# RTM_Connector.net
KiCad netlist of a schematic drawn in Altium Designer
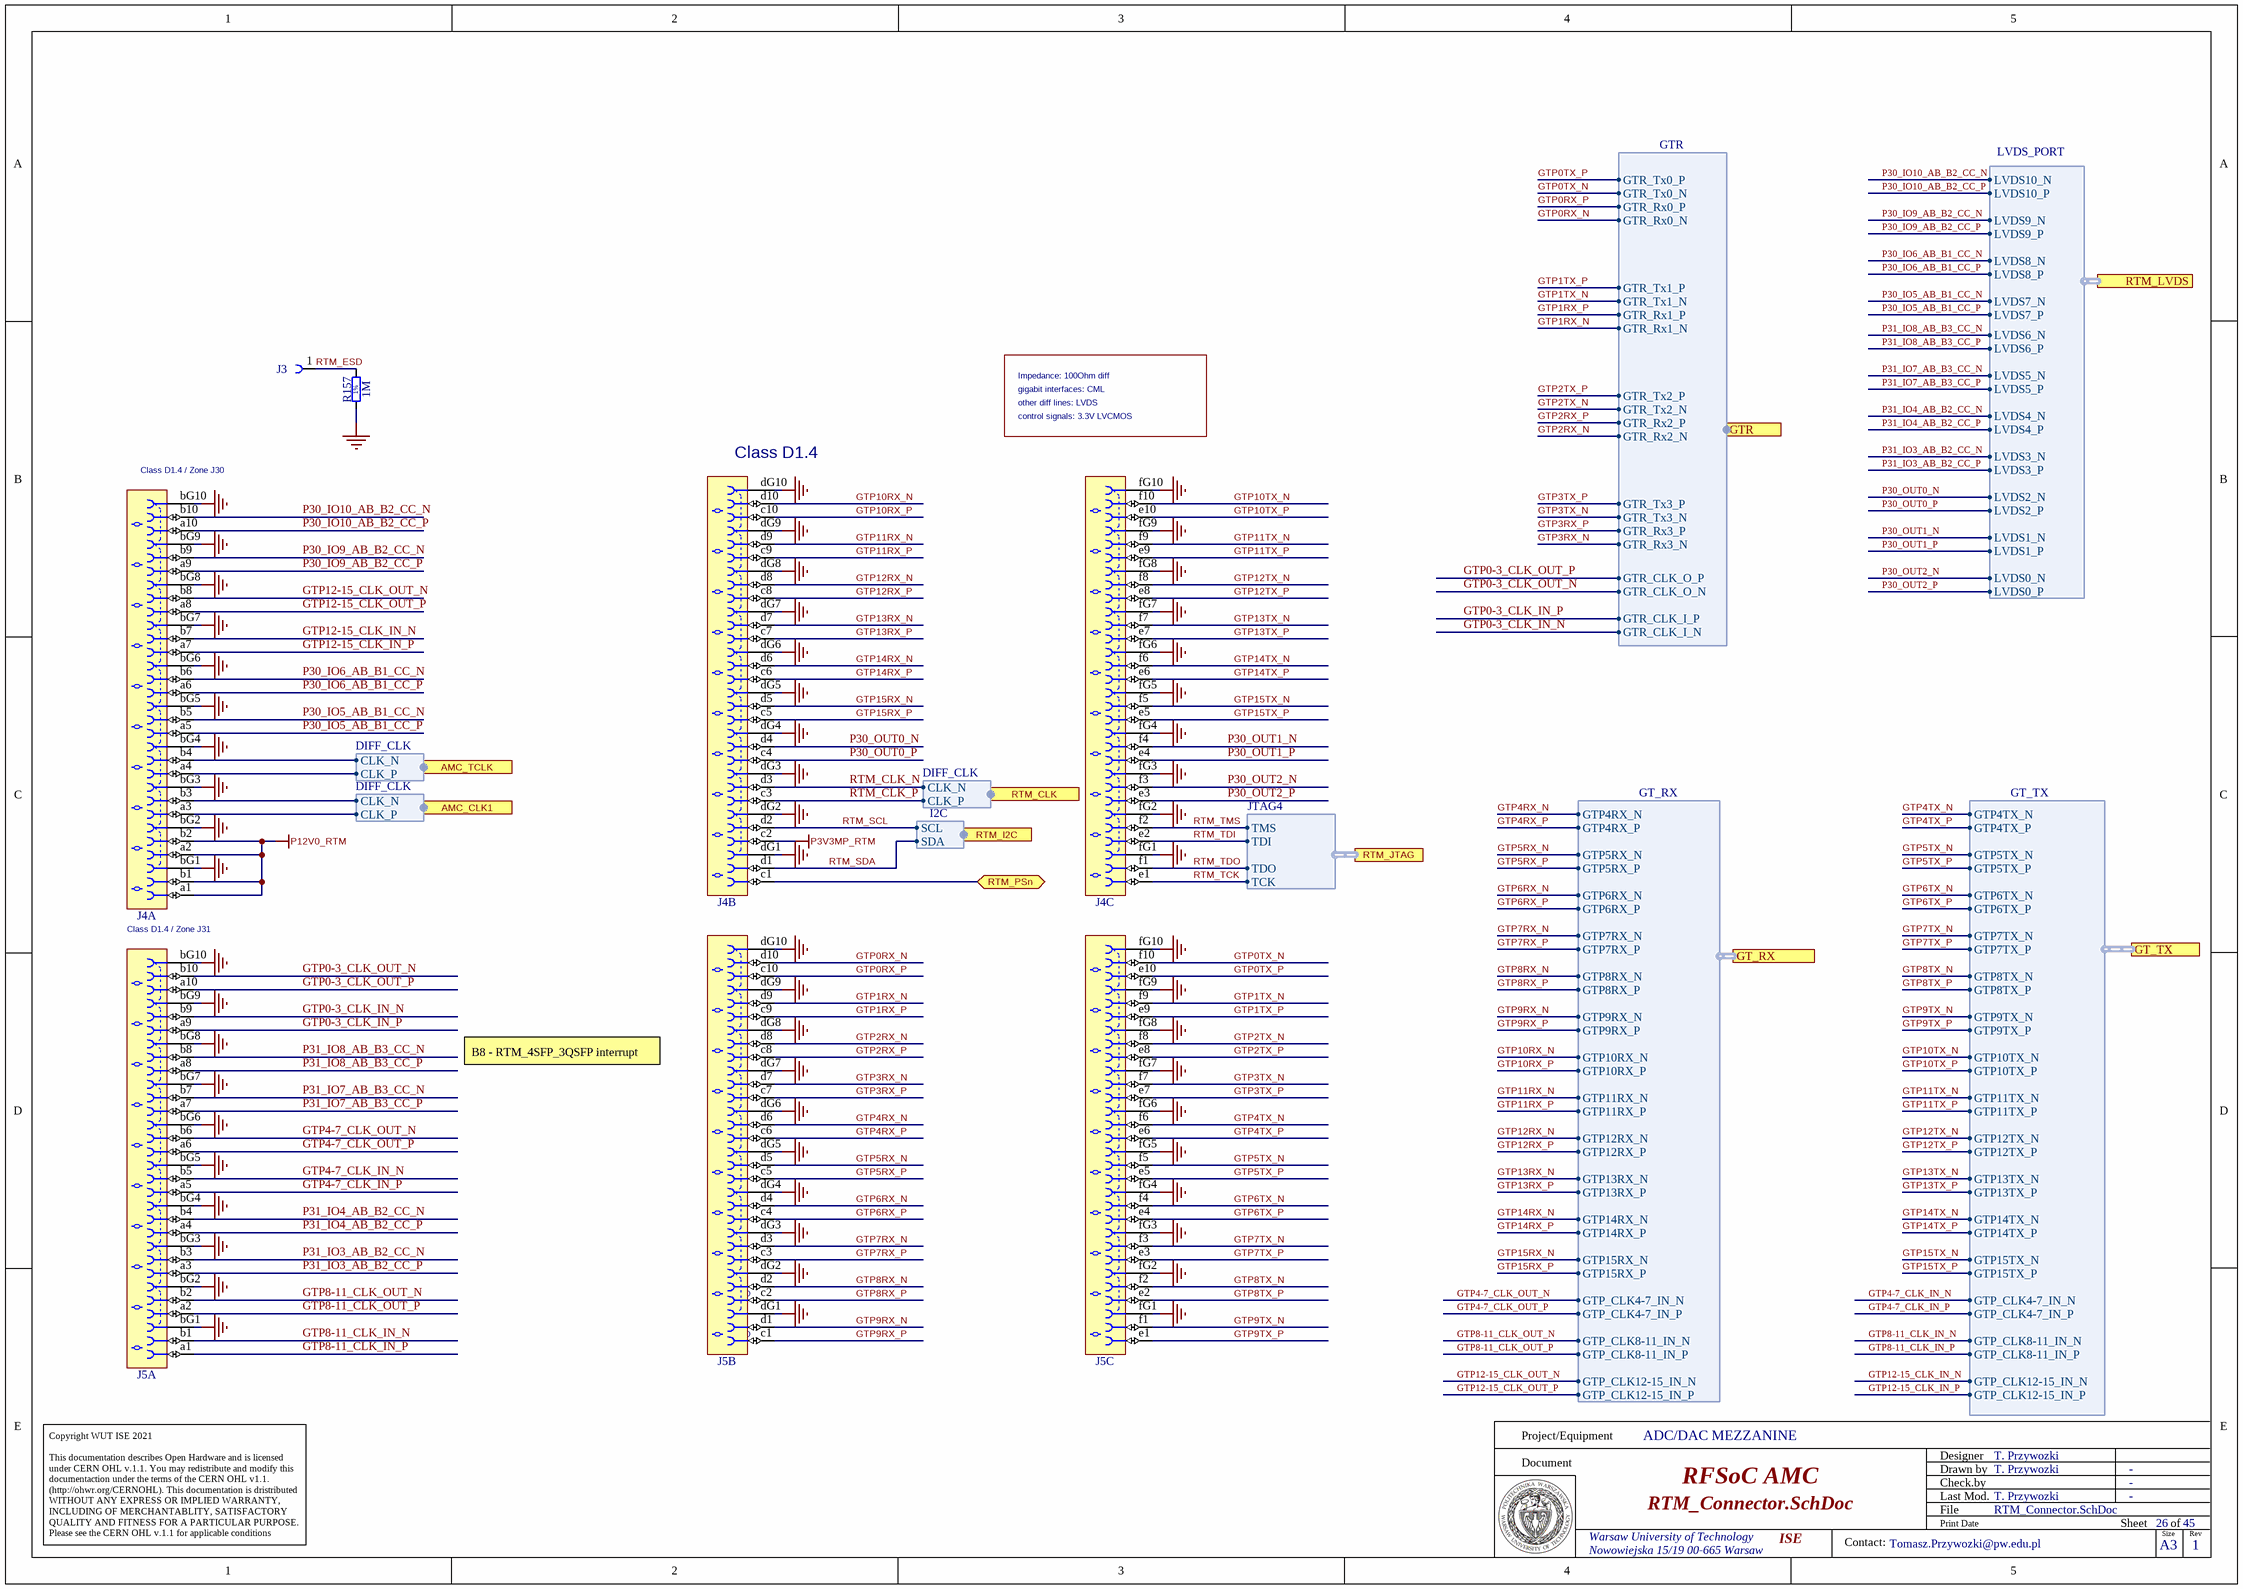
[diagram p0: RTM_Connector.SchDoc]

(export (version "E")
  (design (tool "Eeschema 10.0.6"))
  (components
    (comp (ref "J3")
      (value "~")
      (footprint "TYCO_5120913-1")
      (description "Single Pin Female")
      (fields
        (field (name "MANUFACTURER PART NUMBER") "5120913-1")
        (field (name "MANUFACTURER") "TYCO ELECTRONICS")
        (field (name "AUTHOR") "CERN DEM JLC")
      )
      (libsource (lib "Connectors") (part "Single Pin Female"))
    )
    (comp (ref "J4")
      (value "Advanced TCA")
      (footprint "TYCO_6469081-1")
      (description "Connector 60 ATCA Female 30 Pairs (60 Signals) + 3x10 Ground")
      (fields
        (field (name "MANUFACTURER PART NUMBER") "6469081-1")
        (field (name "MANUFACTURER") "TYCO ELECTRONICS")
        (field (name "AUTHOR") "CERN DEM JLC")
      )
      (libsource (lib "Connectors") (part "Connector ATCA 60+30 Female"))
    )
    (comp (ref "J5")
      (value "Advanced TCA")
      (footprint "TYCO_6469081-1")
      (description "Connector 60 ATCA Female 30 Pairs (60 Signals) + 3x10 Ground")
      (fields
        (field (name "MANUFACTURER PART NUMBER") "6469081-1")
        (field (name "MANUFACTURER") "TYCO ELECTRONICS")
        (field (name "AUTHOR") "CERN DEM JLC")
      )
      (libsource (lib "Connectors") (part "Connector ATCA 60+30 Female"))
    )
    (comp (ref "R157")
      (value "1M")
      (footprint "RESC5025X65N")
      (description "Resistor - 1%")
      (fields
        (field (name "MANUFACTURER PART NUMBER") "R2010_1M_1%_0.5W_200PPM")
        (field (name "MANUFACTURER") "GENERIC")
        (field (name "AUTHOR") "CERN DEM JLC")
      )
      (libsource (lib "Resistors") (part "Resistor - 1%"))
    )
  )
  (nets
    (net (code "8") (name "/GTP0-3_CLK_IN_N") (class "Default")
      (node (ref "J5") (pin "b9") (pinfunction "b9_b9") (pintype "bidirectional"))
    )
    (net (code "9") (name "/GTP0-3_CLK_IN_P") (class "Default")
      (node (ref "J5") (pin "a9") (pinfunction "a9_a9") (pintype "bidirectional"))
    )
    (net (code "10") (name "/GTP0-3_CLK_OUT_N") (class "Default")
      (node (ref "J5") (pin "b10") (pinfunction "b10_b10") (pintype "bidirectional"))
    )
    (net (code "11") (name "/GTP0-3_CLK_OUT_P") (class "Default")
      (node (ref "J5") (pin "a10") (pinfunction "a10_a10") (pintype "bidirectional"))
    )
    (net (code "12") (name "/GTP0RX_N") (class "Default")
      (node (ref "J5") (pin "d10") (pinfunction "d10_d10") (pintype "bidirectional"))
    )
    (net (code "13") (name "/GTP0RX_P") (class "Default")
      (node (ref "J5") (pin "c10") (pinfunction "c10_c10") (pintype "bidirectional"))
    )
    (net (code "14") (name "/GTP0TX_N") (class "Default")
      (node (ref "J5") (pin "f10") (pinfunction "f10_f10") (pintype "bidirectional"))
    )
    (net (code "15") (name "/GTP0TX_P") (class "Default")
      (node (ref "J5") (pin "e10") (pinfunction "e10_e10") (pintype "bidirectional"))
    )
    (net (code "16") (name "/GTP1RX_N") (class "Default")
      (node (ref "J5") (pin "d9") (pinfunction "d9_d9") (pintype "bidirectional"))
    )
    (net (code "17") (name "/GTP1RX_P") (class "Default")
      (node (ref "J5") (pin "c9") (pinfunction "c9_c9") (pintype "bidirectional"))
    )
    (net (code "18") (name "/GTP1TX_N") (class "Default")
      (node (ref "J5") (pin "f9") (pinfunction "f9_f9") (pintype "bidirectional"))
    )
    (net (code "19") (name "/GTP1TX_P") (class "Default")
      (node (ref "J5") (pin "e9") (pinfunction "e9_e9") (pintype "bidirectional"))
    )
    (net (code "20") (name "/GTP2RX_N") (class "Default")
      (node (ref "J5") (pin "d8") (pinfunction "d8_d8") (pintype "bidirectional"))
    )
    (net (code "21") (name "/GTP2RX_P") (class "Default")
      (node (ref "J5") (pin "c8") (pinfunction "c8_c8") (pintype "bidirectional"))
    )
    (net (code "22") (name "/GTP2TX_N") (class "Default")
      (node (ref "J5") (pin "f8") (pinfunction "f8_f8") (pintype "bidirectional"))
    )
    (net (code "23") (name "/GTP2TX_P") (class "Default")
      (node (ref "J5") (pin "e8") (pinfunction "e8_e8") (pintype "bidirectional"))
    )
    (net (code "24") (name "/GTP3RX_N") (class "Default")
      (node (ref "J5") (pin "d7") (pinfunction "d7_d7") (pintype "bidirectional"))
    )
    (net (code "25") (name "/GTP3RX_P") (class "Default")
      (node (ref "J5") (pin "c7") (pinfunction "c7_c7") (pintype "bidirectional"))
    )
    (net (code "26") (name "/GTP3TX_N") (class "Default")
      (node (ref "J5") (pin "f7") (pinfunction "f7_f7") (pintype "bidirectional"))
    )
    (net (code "27") (name "/GTP3TX_P") (class "Default")
      (node (ref "J5") (pin "e7") (pinfunction "e7_e7") (pintype "bidirectional"))
    )
    (net (code "28") (name "/GTP4-7_CLK_IN_N") (class "Default")
      (node (ref "J5") (pin "b5") (pinfunction "b5_b5") (pintype "bidirectional"))
    )
    (net (code "29") (name "/GTP4-7_CLK_IN_P") (class "Default")
      (node (ref "J5") (pin "a5") (pinfunction "a5_a5") (pintype "bidirectional"))
    )
    (net (code "30") (name "/GTP4-7_CLK_OUT_N") (class "Default")
      (node (ref "J5") (pin "b6") (pinfunction "b6_b6") (pintype "bidirectional"))
    )
    (net (code "31") (name "/GTP4-7_CLK_OUT_P") (class "Default")
      (node (ref "J5") (pin "a6") (pinfunction "a6_a6") (pintype "bidirectional"))
    )
    (net (code "32") (name "/GTP4RX_N") (class "Default")
      (node (ref "J5") (pin "d6") (pinfunction "d6_d6") (pintype "bidirectional"))
    )
    (net (code "33") (name "/GTP4RX_P") (class "Default")
      (node (ref "J5") (pin "c6") (pinfunction "c6_c6") (pintype "bidirectional"))
    )
    (net (code "34") (name "/GTP4TX_N") (class "Default")
      (node (ref "J5") (pin "f6") (pinfunction "f6_f6") (pintype "bidirectional"))
    )
    (net (code "35") (name "/GTP4TX_P") (class "Default")
      (node (ref "J5") (pin "e6") (pinfunction "e6_e6") (pintype "bidirectional"))
    )
    (net (code "36") (name "/GTP5RX_N") (class "Default")
      (node (ref "J5") (pin "d5") (pinfunction "d5_d5") (pintype "bidirectional"))
    )
    (net (code "37") (name "/GTP5RX_P") (class "Default")
      (node (ref "J5") (pin "c5") (pinfunction "c5_c5") (pintype "bidirectional"))
    )
    (net (code "38") (name "/GTP5TX_N") (class "Default")
      (node (ref "J5") (pin "f5") (pinfunction "f5_f5") (pintype "bidirectional"))
    )
    (net (code "39") (name "/GTP5TX_P") (class "Default")
      (node (ref "J5") (pin "e5") (pinfunction "e5_e5") (pintype "bidirectional"))
    )
    (net (code "40") (name "/GTP6RX_N") (class "Default")
      (node (ref "J5") (pin "d4") (pinfunction "d4_d4") (pintype "bidirectional"))
    )
    (net (code "41") (name "/GTP6RX_P") (class "Default")
      (node (ref "J5") (pin "c4") (pinfunction "c4_c4") (pintype "bidirectional"))
    )
    (net (code "42") (name "/GTP6TX_N") (class "Default")
      (node (ref "J5") (pin "f4") (pinfunction "f4_f4") (pintype "bidirectional"))
    )
    (net (code "43") (name "/GTP6TX_P") (class "Default")
      (node (ref "J5") (pin "e4") (pinfunction "e4_e4") (pintype "bidirectional"))
    )
    (net (code "44") (name "/GTP7RX_N") (class "Default")
      (node (ref "J5") (pin "d3") (pinfunction "d3_d3") (pintype "bidirectional"))
    )
    (net (code "45") (name "/GTP7RX_P") (class "Default")
      (node (ref "J5") (pin "c3") (pinfunction "c3_c3") (pintype "bidirectional"))
    )
    (net (code "46") (name "/GTP7TX_N") (class "Default")
      (node (ref "J5") (pin "f3") (pinfunction "f3_f3") (pintype "bidirectional"))
    )
    (net (code "47") (name "/GTP7TX_P") (class "Default")
      (node (ref "J5") (pin "e3") (pinfunction "e3_e3") (pintype "bidirectional"))
    )
    (net (code "48") (name "/GTP8-11_CLK_IN_N") (class "Default")
      (node (ref "J5") (pin "b1") (pinfunction "b1_b1") (pintype "bidirectional"))
    )
    (net (code "49") (name "/GTP8-11_CLK_IN_P") (class "Default")
      (node (ref "J5") (pin "a1") (pinfunction "a1_a1") (pintype "bidirectional"))
    )
    (net (code "50") (name "/GTP8-11_CLK_OUT_N") (class "Default")
      (node (ref "J5") (pin "b2") (pinfunction "b2_b2") (pintype "bidirectional"))
    )
    (net (code "51") (name "/GTP8-11_CLK_OUT_P") (class "Default")
      (node (ref "J5") (pin "a2") (pinfunction "a2_a2") (pintype "bidirectional"))
    )
    (net (code "52") (name "/GTP8RX_N") (class "Default")
      (node (ref "J5") (pin "d2") (pinfunction "d2_d2") (pintype "bidirectional"))
    )
    (net (code "53") (name "/GTP8RX_P") (class "Default")
      (node (ref "J5") (pin "c2") (pinfunction "c2_c2") (pintype "bidirectional"))
    )
    (net (code "54") (name "/GTP8TX_N") (class "Default")
      (node (ref "J5") (pin "f2") (pinfunction "f2_f2") (pintype "bidirectional"))
    )
    (net (code "55") (name "/GTP8TX_P") (class "Default")
      (node (ref "J5") (pin "e2") (pinfunction "e2_e2") (pintype "bidirectional"))
    )
    (net (code "56") (name "/GTP9RX_N") (class "Default")
      (node (ref "J5") (pin "d1") (pinfunction "d1_d1") (pintype "bidirectional"))
    )
    (net (code "57") (name "/GTP9RX_P") (class "Default")
      (node (ref "J5") (pin "c1") (pinfunction "c1_c1") (pintype "bidirectional"))
    )
    (net (code "58") (name "/GTP9TX_N") (class "Default")
      (node (ref "J5") (pin "f1") (pinfunction "f1_f1") (pintype "bidirectional"))
    )
    (net (code "59") (name "/GTP9TX_P") (class "Default")
      (node (ref "J5") (pin "e1") (pinfunction "e1_e1") (pintype "bidirectional"))
    )
    (net (code "60") (name "/GTP10RX_N") (class "Default")
      (node (ref "J4") (pin "d10") (pinfunction "d10_d10") (pintype "bidirectional"))
    )
    (net (code "61") (name "/GTP10RX_P") (class "Default")
      (node (ref "J4") (pin "c10") (pinfunction "c10_c10") (pintype "bidirectional"))
    )
    (net (code "62") (name "/GTP10TX_N") (class "Default")
      (node (ref "J4") (pin "f10") (pinfunction "f10_f10") (pintype "bidirectional"))
    )
    (net (code "63") (name "/GTP10TX_P") (class "Default")
      (node (ref "J4") (pin "e10") (pinfunction "e10_e10") (pintype "bidirectional"))
    )
    (net (code "64") (name "/GTP11RX_N") (class "Default")
      (node (ref "J4") (pin "d9") (pinfunction "d9_d9") (pintype "bidirectional"))
    )
    (net (code "65") (name "/GTP11RX_P") (class "Default")
      (node (ref "J4") (pin "c9") (pinfunction "c9_c9") (pintype "bidirectional"))
    )
    (net (code "66") (name "/GTP11TX_N") (class "Default")
      (node (ref "J4") (pin "f9") (pinfunction "f9_f9") (pintype "bidirectional"))
    )
    (net (code "67") (name "/GTP11TX_P") (class "Default")
      (node (ref "J4") (pin "e9") (pinfunction "e9_e9") (pintype "bidirectional"))
    )
    (net (code "68") (name "/GTP12-15_CLK_IN_N") (class "Default")
      (node (ref "J4") (pin "b7") (pinfunction "b7_b7") (pintype "bidirectional"))
    )
    (net (code "69") (name "/GTP12-15_CLK_IN_P") (class "Default")
      (node (ref "J4") (pin "a7") (pinfunction "a7_a7") (pintype "bidirectional"))
    )
    (net (code "70") (name "/GTP12-15_CLK_OUT_N") (class "Default")
      (node (ref "J4") (pin "b8") (pinfunction "b8_b8") (pintype "bidirectional"))
    )
    (net (code "71") (name "/GTP12-15_CLK_OUT_P") (class "Default")
      (node (ref "J4") (pin "a8") (pinfunction "a8_a8") (pintype "bidirectional"))
    )
    (net (code "72") (name "/GTP12RX_N") (class "Default")
      (node (ref "J4") (pin "d8") (pinfunction "d8_d8") (pintype "bidirectional"))
    )
    (net (code "73") (name "/GTP12RX_P") (class "Default")
      (node (ref "J4") (pin "c8") (pinfunction "c8_c8") (pintype "bidirectional"))
    )
    (net (code "74") (name "/GTP12TX_N") (class "Default")
      (node (ref "J4") (pin "f8") (pinfunction "f8_f8") (pintype "bidirectional"))
    )
    (net (code "75") (name "/GTP12TX_P") (class "Default")
      (node (ref "J4") (pin "e8") (pinfunction "e8_e8") (pintype "bidirectional"))
    )
    (net (code "76") (name "/GTP13RX_N") (class "Default")
      (node (ref "J4") (pin "d7") (pinfunction "d7_d7") (pintype "bidirectional"))
    )
    (net (code "77") (name "/GTP13RX_P") (class "Default")
      (node (ref "J4") (pin "c7") (pinfunction "c7_c7") (pintype "bidirectional"))
    )
    (net (code "78") (name "/GTP13TX_N") (class "Default")
      (node (ref "J4") (pin "f7") (pinfunction "f7_f7") (pintype "bidirectional"))
    )
    (net (code "79") (name "/GTP13TX_P") (class "Default")
      (node (ref "J4") (pin "e7") (pinfunction "e7_e7") (pintype "bidirectional"))
    )
    (net (code "80") (name "/GTP14RX_N") (class "Default")
      (node (ref "J4") (pin "d6") (pinfunction "d6_d6") (pintype "bidirectional"))
    )
    (net (code "81") (name "/GTP14RX_P") (class "Default")
      (node (ref "J4") (pin "c6") (pinfunction "c6_c6") (pintype "bidirectional"))
    )
    (net (code "82") (name "/GTP14TX_N") (class "Default")
      (node (ref "J4") (pin "f6") (pinfunction "f6_f6") (pintype "bidirectional"))
    )
    (net (code "83") (name "/GTP14TX_P") (class "Default")
      (node (ref "J4") (pin "e6") (pinfunction "e6_e6") (pintype "bidirectional"))
    )
    (net (code "84") (name "/GTP15RX_N") (class "Default")
      (node (ref "J4") (pin "d5") (pinfunction "d5_d5") (pintype "bidirectional"))
    )
    (net (code "85") (name "/GTP15RX_P") (class "Default")
      (node (ref "J4") (pin "c5") (pinfunction "c5_c5") (pintype "bidirectional"))
    )
    (net (code "86") (name "/GTP15TX_N") (class "Default")
      (node (ref "J4") (pin "f5") (pinfunction "f5_f5") (pintype "bidirectional"))
    )
    (net (code "87") (name "/GTP15TX_P") (class "Default")
      (node (ref "J4") (pin "e5") (pinfunction "e5_e5") (pintype "bidirectional"))
    )
    (net (code "88") (name "/P30_IO5_AB_B1_CC_N") (class "Default")
      (node (ref "J4") (pin "b5") (pinfunction "b5_b5") (pintype "bidirectional"))
    )
    (net (code "89") (name "/P30_IO5_AB_B1_CC_P") (class "Default")
      (node (ref "J4") (pin "a5") (pinfunction "a5_a5") (pintype "bidirectional"))
    )
    (net (code "90") (name "/P30_IO6_AB_B1_CC_N") (class "Default")
      (node (ref "J4") (pin "b6") (pinfunction "b6_b6") (pintype "bidirectional"))
    )
    (net (code "91") (name "/P30_IO6_AB_B1_CC_P") (class "Default")
      (node (ref "J4") (pin "a6") (pinfunction "a6_a6") (pintype "bidirectional"))
    )
    (net (code "92") (name "/P30_IO9_AB_B2_CC_N") (class "Default")
      (node (ref "J4") (pin "b9") (pinfunction "b9_b9") (pintype "bidirectional"))
    )
    (net (code "93") (name "/P30_IO9_AB_B2_CC_P") (class "Default")
      (node (ref "J4") (pin "a9") (pinfunction "a9_a9") (pintype "bidirectional"))
    )
    (net (code "94") (name "/P30_IO10_AB_B2_CC_N") (class "Default")
      (node (ref "J4") (pin "b10") (pinfunction "b10_b10") (pintype "bidirectional"))
    )
    (net (code "95") (name "/P30_IO10_AB_B2_CC_P") (class "Default")
      (node (ref "J4") (pin "a10") (pinfunction "a10_a10") (pintype "bidirectional"))
    )
    (net (code "96") (name "/P30_OUT0_N") (class "Default")
      (node (ref "J4") (pin "d4") (pinfunction "d4_d4") (pintype "bidirectional"))
    )
    (net (code "97") (name "/P30_OUT0_P") (class "Default")
      (node (ref "J4") (pin "c4") (pinfunction "c4_c4") (pintype "bidirectional"))
    )
    (net (code "98") (name "/P30_OUT1_N") (class "Default")
      (node (ref "J4") (pin "f4") (pinfunction "f4_f4") (pintype "bidirectional"))
    )
    (net (code "99") (name "/P30_OUT1_P") (class "Default")
      (node (ref "J4") (pin "e4") (pinfunction "e4_e4") (pintype "bidirectional"))
    )
    (net (code "100") (name "/P30_OUT2_N") (class "Default")
      (node (ref "J4") (pin "f3") (pinfunction "f3_f3") (pintype "bidirectional"))
    )
    (net (code "101") (name "/P30_OUT2_P") (class "Default")
      (node (ref "J4") (pin "e3") (pinfunction "e3_e3") (pintype "bidirectional"))
    )
    (net (code "102") (name "/P31_IO3_AB_B2_CC_N") (class "Default")
      (node (ref "J5") (pin "b3") (pinfunction "b3_b3") (pintype "bidirectional"))
    )
    (net (code "103") (name "/P31_IO3_AB_B2_CC_P") (class "Default")
      (node (ref "J5") (pin "a3") (pinfunction "a3_a3") (pintype "bidirectional"))
    )
    (net (code "104") (name "/P31_IO4_AB_B2_CC_N") (class "Default")
      (node (ref "J5") (pin "b4") (pinfunction "b4_b4") (pintype "bidirectional"))
    )
    (net (code "105") (name "/P31_IO4_AB_B2_CC_P") (class "Default")
      (node (ref "J5") (pin "a4") (pinfunction "a4_a4") (pintype "bidirectional"))
    )
    (net (code "106") (name "/P31_IO7_AB_B3_CC_N") (class "Default")
      (node (ref "J5") (pin "b7") (pinfunction "b7_b7") (pintype "bidirectional"))
    )
    (net (code "107") (name "/P31_IO7_AB_B3_CC_P") (class "Default")
      (node (ref "J5") (pin "a7") (pinfunction "a7_a7") (pintype "bidirectional"))
    )
    (net (code "108") (name "/P31_IO8_AB_B3_CC_N") (class "Default")
      (node (ref "J5") (pin "b8") (pinfunction "b8_b8") (pintype "bidirectional"))
    )
    (net (code "109") (name "/P31_IO8_AB_B3_CC_P") (class "Default")
      (node (ref "J5") (pin "a8") (pinfunction "a8_a8") (pintype "bidirectional"))
    )
    (net (code "110") (name "/RTM_CLK_N") (class "Default")
      (node (ref "J4") (pin "d3") (pinfunction "d3_d3") (pintype "bidirectional"))
    )
    (net (code "111") (name "/RTM_CLK_P") (class "Default")
      (node (ref "J4") (pin "c3") (pinfunction "c3_c3") (pintype "bidirectional"))
    )
    (net (code "112") (name "/RTM_ESD") (class "Default")
      (node (ref "J3") (pin "1") (pinfunction "1_1") (pintype "bidirectional"))
      (node (ref "R157") (pin "2") (pinfunction "2_2") (pintype "passive"))
    )
    (net (code "113") (name "/RTM_PSn") (class "Default")
      (node (ref "J4") (pin "c1") (pinfunction "c1_c1") (pintype "bidirectional"))
    )
    (net (code "114") (name "/RTM_SCL") (class "Default")
      (node (ref "J4") (pin "d2") (pinfunction "d2_d2") (pintype "bidirectional"))
    )
    (net (code "115") (name "/RTM_SDA") (class "Default")
      (node (ref "J4") (pin "d1") (pinfunction "d1_d1") (pintype "bidirectional"))
    )
    (net (code "116") (name "/RTM_TCK") (class "Default")
      (node (ref "J4") (pin "e1") (pinfunction "e1_e1") (pintype "bidirectional"))
    )
    (net (code "117") (name "/RTM_TDI") (class "Default")
      (node (ref "J4") (pin "e2") (pinfunction "e2_e2") (pintype "bidirectional"))
    )
    (net (code "118") (name "/RTM_TDO") (class "Default")
      (node (ref "J4") (pin "f1") (pinfunction "f1_f1") (pintype "bidirectional"))
    )
    (net (code "119") (name "/RTM_TMS") (class "Default")
      (node (ref "J4") (pin "f2") (pinfunction "f2_f2") (pintype "bidirectional"))
    )
    (net (code "127") (name "GND") (class "Default")
      (node (ref "J4") (pin "bG1") (pinfunction "bG1_bG1") (pintype "power_in"))
      (node (ref "J4") (pin "bG10") (pinfunction "bG10_bG10") (pintype "power_in"))
      (node (ref "J4") (pin "bG2") (pinfunction "bG2_bG2") (pintype "power_in"))
      (node (ref "J4") (pin "bG3") (pinfunction "bG3_bG3") (pintype "power_in"))
      (node (ref "J4") (pin "bG4") (pinfunction "bG4_bG4") (pintype "power_in"))
      (node (ref "J4") (pin "bG5") (pinfunction "bG5_bG5") (pintype "power_in"))
      (node (ref "J4") (pin "bG6") (pinfunction "bG6_bG6") (pintype "power_in"))
      (node (ref "J4") (pin "bG7") (pinfunction "bG7_bG7") (pintype "power_in"))
      (node (ref "J4") (pin "bG8") (pinfunction "bG8_bG8") (pintype "power_in"))
      (node (ref "J4") (pin "bG9") (pinfunction "bG9_bG9") (pintype "power_in"))
      (node (ref "J4") (pin "dG1") (pinfunction "dG1_dG1") (pintype "power_in"))
      (node (ref "J4") (pin "dG10") (pinfunction "dG10_dG10") (pintype "power_in"))
      (node (ref "J4") (pin "dG2") (pinfunction "dG2_dG2") (pintype "power_in"))
      (node (ref "J4") (pin "dG3") (pinfunction "dG3_dG3") (pintype "power_in"))
      (node (ref "J4") (pin "dG4") (pinfunction "dG4_dG4") (pintype "power_in"))
      (node (ref "J4") (pin "dG5") (pinfunction "dG5_dG5") (pintype "power_in"))
      (node (ref "J4") (pin "dG6") (pinfunction "dG6_dG6") (pintype "power_in"))
      (node (ref "J4") (pin "dG7") (pinfunction "dG7_dG7") (pintype "power_in"))
      (node (ref "J4") (pin "dG8") (pinfunction "dG8_dG8") (pintype "power_in"))
      (node (ref "J4") (pin "dG9") (pinfunction "dG9_dG9") (pintype "power_in"))
      (node (ref "J4") (pin "fG1") (pinfunction "fG1_fG1") (pintype "power_in"))
      (node (ref "J4") (pin "fG10") (pinfunction "fG10_fG10") (pintype "power_in"))
      (node (ref "J4") (pin "fG2") (pinfunction "fG2_fG2") (pintype "power_in"))
      (node (ref "J4") (pin "fG3") (pinfunction "fG3_fG3") (pintype "power_in"))
      (node (ref "J4") (pin "fG4") (pinfunction "fG4_fG4") (pintype "power_in"))
      (node (ref "J4") (pin "fG5") (pinfunction "fG5_fG5") (pintype "power_in"))
      (node (ref "J4") (pin "fG6") (pinfunction "fG6_fG6") (pintype "power_in"))
      (node (ref "J4") (pin "fG7") (pinfunction "fG7_fG7") (pintype "power_in"))
      (node (ref "J4") (pin "fG8") (pinfunction "fG8_fG8") (pintype "power_in"))
      (node (ref "J4") (pin "fG9") (pinfunction "fG9_fG9") (pintype "power_in"))
      (node (ref "J5") (pin "bG1") (pinfunction "bG1_bG1") (pintype "power_in"))
      (node (ref "J5") (pin "bG10") (pinfunction "bG10_bG10") (pintype "power_in"))
      (node (ref "J5") (pin "bG2") (pinfunction "bG2_bG2") (pintype "power_in"))
      (node (ref "J5") (pin "bG3") (pinfunction "bG3_bG3") (pintype "power_in"))
      (node (ref "J5") (pin "bG4") (pinfunction "bG4_bG4") (pintype "power_in"))
      (node (ref "J5") (pin "bG5") (pinfunction "bG5_bG5") (pintype "power_in"))
      (node (ref "J5") (pin "bG6") (pinfunction "bG6_bG6") (pintype "power_in"))
      (node (ref "J5") (pin "bG7") (pinfunction "bG7_bG7") (pintype "power_in"))
      (node (ref "J5") (pin "bG8") (pinfunction "bG8_bG8") (pintype "power_in"))
      (node (ref "J5") (pin "bG9") (pinfunction "bG9_bG9") (pintype "power_in"))
      (node (ref "J5") (pin "dG1") (pinfunction "dG1_dG1") (pintype "power_in"))
      (node (ref "J5") (pin "dG10") (pinfunction "dG10_dG10") (pintype "power_in"))
      (node (ref "J5") (pin "dG2") (pinfunction "dG2_dG2") (pintype "power_in"))
      (node (ref "J5") (pin "dG3") (pinfunction "dG3_dG3") (pintype "power_in"))
      (node (ref "J5") (pin "dG4") (pinfunction "dG4_dG4") (pintype "power_in"))
      (node (ref "J5") (pin "dG5") (pinfunction "dG5_dG5") (pintype "power_in"))
      (node (ref "J5") (pin "dG6") (pinfunction "dG6_dG6") (pintype "power_in"))
      (node (ref "J5") (pin "dG7") (pinfunction "dG7_dG7") (pintype "power_in"))
      (node (ref "J5") (pin "dG8") (pinfunction "dG8_dG8") (pintype "power_in"))
      (node (ref "J5") (pin "dG9") (pinfunction "dG9_dG9") (pintype "power_in"))
      (node (ref "J5") (pin "fG1") (pinfunction "fG1_fG1") (pintype "power_in"))
      (node (ref "J5") (pin "fG10") (pinfunction "fG10_fG10") (pintype "power_in"))
      (node (ref "J5") (pin "fG2") (pinfunction "fG2_fG2") (pintype "power_in"))
      (node (ref "J5") (pin "fG3") (pinfunction "fG3_fG3") (pintype "power_in"))
      (node (ref "J5") (pin "fG4") (pinfunction "fG4_fG4") (pintype "power_in"))
      (node (ref "J5") (pin "fG5") (pinfunction "fG5_fG5") (pintype "power_in"))
      (node (ref "J5") (pin "fG6") (pinfunction "fG6_fG6") (pintype "power_in"))
      (node (ref "J5") (pin "fG7") (pinfunction "fG7_fG7") (pintype "power_in"))
      (node (ref "J5") (pin "fG8") (pinfunction "fG8_fG8") (pintype "power_in"))
      (node (ref "J5") (pin "fG9") (pinfunction "fG9_fG9") (pintype "power_in"))
      (node (ref "R157") (pin "1") (pinfunction "1_1") (pintype "passive"))
    )
    (net (code "128") (name "P3V3MP_RTM") (class "Default")
      (node (ref "J4") (pin "c2") (pinfunction "c2_c2") (pintype "bidirectional"))
    )
    (net (code "129") (name "P12V0_RTM") (class "Default")
      (node (ref "J4") (pin "a1") (pinfunction "a1_a1") (pintype "bidirectional"))
      (node (ref "J4") (pin "a2") (pinfunction "a2_a2") (pintype "bidirectional"))
      (node (ref "J4") (pin "b1") (pinfunction "b1_b1") (pintype "bidirectional"))
      (node (ref "J4") (pin "b2") (pinfunction "b2_b2") (pintype "bidirectional"))
    )
    (net (code "130") (name "unconnected-(J4-Pada3)") (class "Default")
      (node (ref "J4") (pin "a3") (pinfunction "a3_a3") (pintype "bidirectional"))
    )
    (net (code "131") (name "unconnected-(J4-Pada4)") (class "Default")
      (node (ref "J4") (pin "a4") (pinfunction "a4_a4") (pintype "bidirectional"))
    )
    (net (code "132") (name "unconnected-(J4-Padb3)") (class "Default")
      (node (ref "J4") (pin "b3") (pinfunction "b3_b3") (pintype "bidirectional"))
    )
    (net (code "133") (name "unconnected-(J4-Padb4)") (class "Default")
      (node (ref "J4") (pin "b4") (pinfunction "b4_b4") (pintype "bidirectional"))
    )
  )
)
